# remote_light.net
KiCad netlist of a schematic drawn in EAGLE
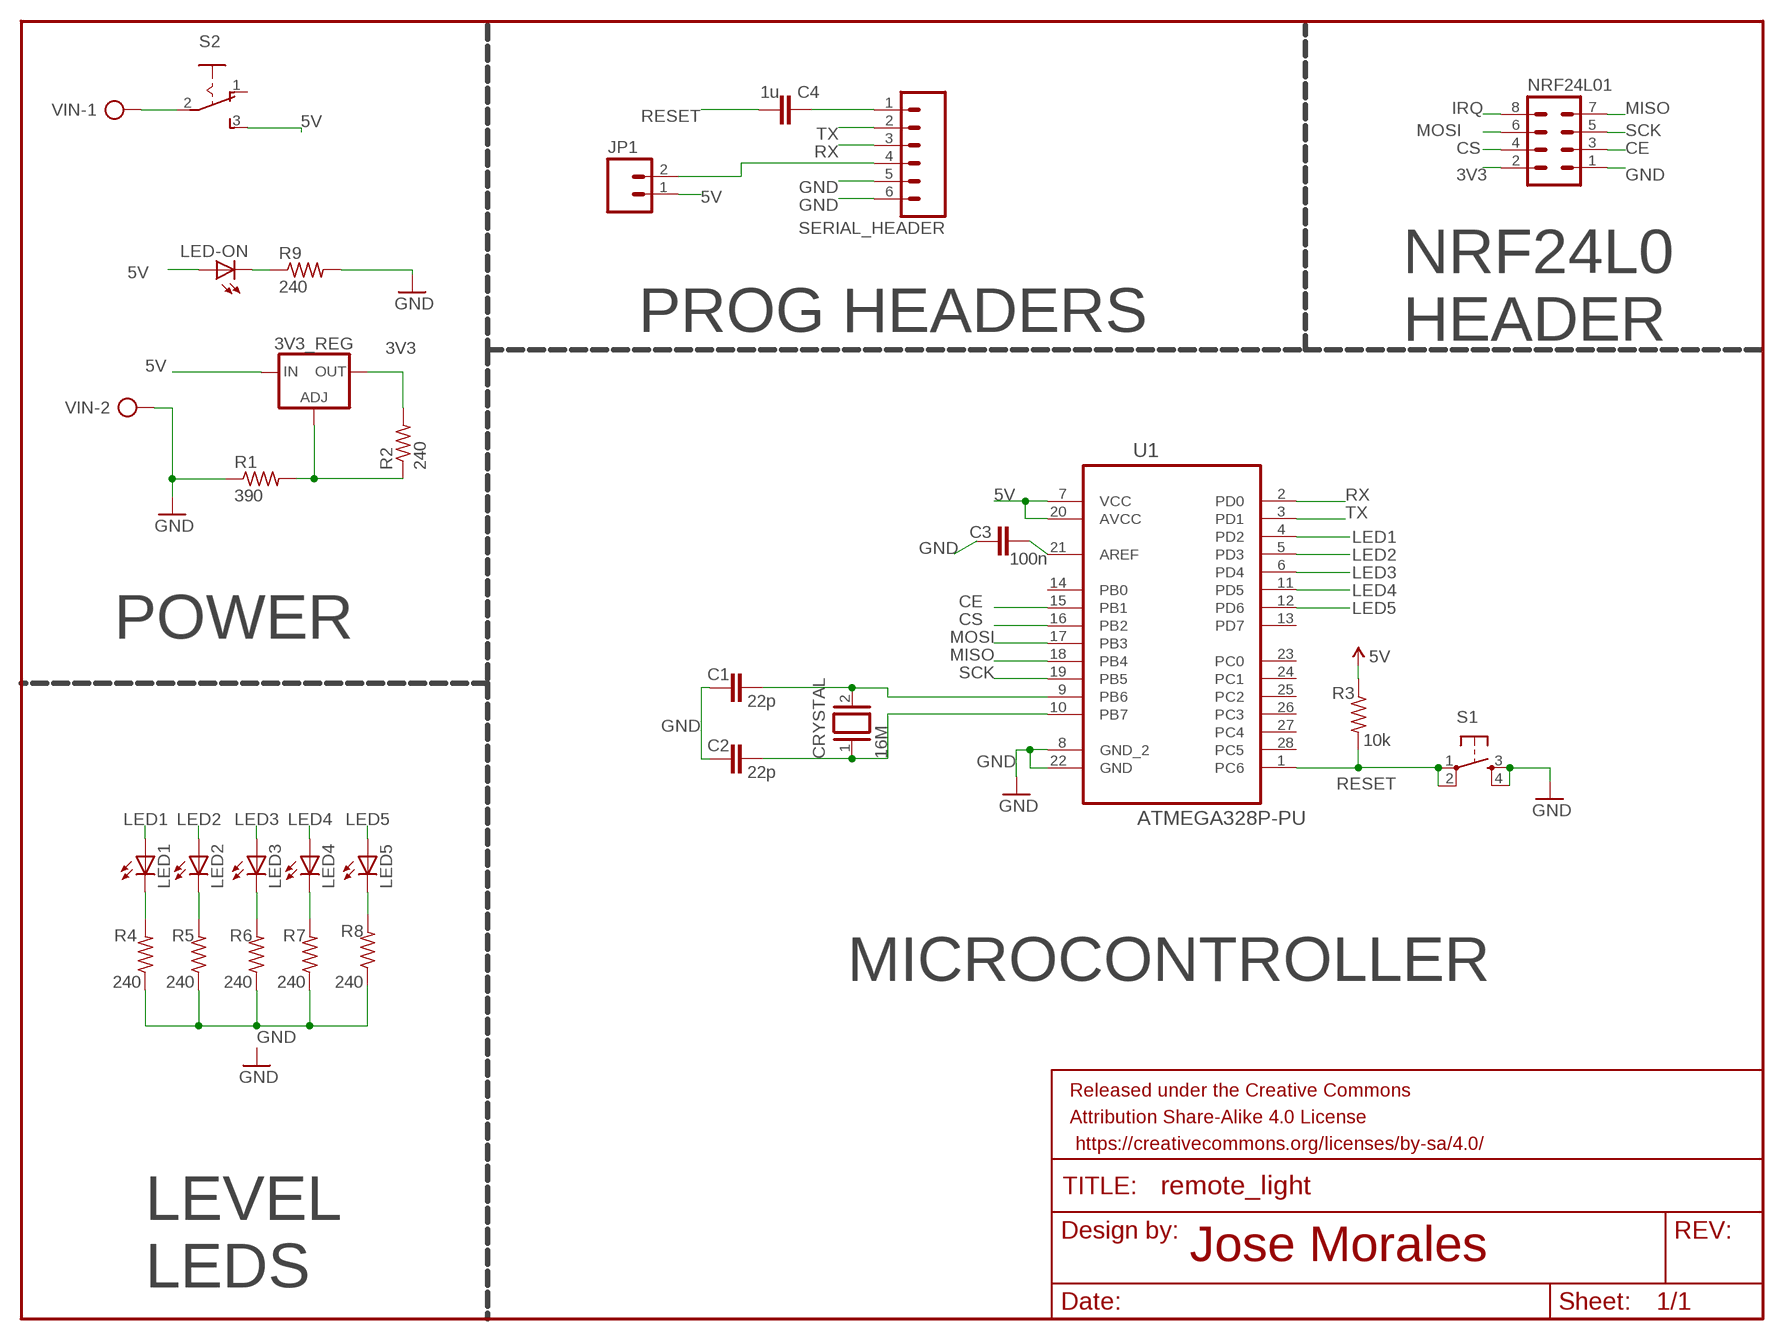
[diagram p0: schematic, sheet 1]

(export (version "E")
  (design (tool "Eeschema 10.0.6"))
  (components
    (comp (ref "C1")
      (value "22p")
      (footprint "eagle-import:C050-025X075")
      (libsource (lib "eagle-import") (part "C-EU050-025X075"))
    )
    (comp (ref "C2")
      (value "22p")
      (footprint "eagle-import:C050-025X075")
      (libsource (lib "eagle-import") (part "C-EU050-025X075"))
    )
    (comp (ref "C3")
      (value "100n")
      (footprint "eagle-import:C050-025X075")
      (libsource (lib "eagle-import") (part "C-EU050-025X075"))
    )
    (comp (ref "C4")
      (value "1u")
      (footprint "eagle-import:C050-025X075")
      (libsource (lib "eagle-import") (part "C-EU050-025X075"))
    )
    (comp (ref "CRYSTAL")
      (value "16M")
      (footprint "eagle-import:QS")
      (libsource (lib "eagle-import") (part "XTAL/S"))
    )
    (comp (ref "FRAME11")
      (value "FRAME-LETTER")
      (footprint "eagle-import:CREATIVE_COMMONS")
      (fields (field (name "DESIGNER") "NAME"))
      (libsource (lib "eagle-import") (part "FRAME-LETTER"))
    )
    (comp (ref "JP1")
      (value "M02LOCK")
      (footprint "eagle-import:1X02_LOCK")
      (libsource (lib "eagle-import") (part "M02LOCK"))
    )
    (comp (ref "LED-ON")
      (value "LED5MM")
      (footprint "eagle-import:LED5MM")
      (libsource (lib "eagle-import") (part "LED5MM"))
    )
    (comp (ref "LED1")
      (value "LED5MM")
      (footprint "eagle-import:LED5MM")
      (libsource (lib "eagle-import") (part "LED5MM"))
    )
    (comp (ref "LED2")
      (value "LED5MM")
      (footprint "eagle-import:LED5MM")
      (libsource (lib "eagle-import") (part "LED5MM"))
    )
    (comp (ref "LED3")
      (value "LED5MM")
      (footprint "eagle-import:LED5MM")
      (libsource (lib "eagle-import") (part "LED5MM"))
    )
    (comp (ref "LED4")
      (value "LED5MM")
      (footprint "eagle-import:LED5MM")
      (libsource (lib "eagle-import") (part "LED5MM"))
    )
    (comp (ref "LED5")
      (value "LED5MM")
      (footprint "eagle-import:LED5MM")
      (libsource (lib "eagle-import") (part "LED5MM"))
    )
    (comp (ref "LM317")
      (value "3V3_REG")
      (footprint "eagle-import:317TS")
      (libsource (lib "eagle-import") (part "LM317TS"))
    )
    (comp (ref "NRF24L01")
      (value "MA04-2")
      (footprint "eagle-import:MA04-2")
      (libsource (lib "eagle-import") (part "MA04-2"))
    )
    (comp (ref "R1")
      (value "390")
      (footprint "eagle-import:0207_12")
      (libsource (lib "eagle-import") (part "R-US_0207/12"))
    )
    (comp (ref "R2")
      (value "240")
      (footprint "eagle-import:0207_12")
      (libsource (lib "eagle-import") (part "R-US_0207/12"))
    )
    (comp (ref "R3")
      (value "10k")
      (footprint "eagle-import:0207_12")
      (libsource (lib "eagle-import") (part "R-US_0207/12"))
    )
    (comp (ref "R4")
      (value "240")
      (footprint "eagle-import:0207_12")
      (libsource (lib "eagle-import") (part "R-US_0207/12"))
    )
    (comp (ref "R5")
      (value "240")
      (footprint "eagle-import:0207_12")
      (libsource (lib "eagle-import") (part "R-US_0207/12"))
    )
    (comp (ref "R6")
      (value "240")
      (footprint "eagle-import:0207_12")
      (libsource (lib "eagle-import") (part "R-US_0207/12"))
    )
    (comp (ref "R7")
      (value "240")
      (footprint "eagle-import:0207_12")
      (libsource (lib "eagle-import") (part "R-US_0207/12"))
    )
    (comp (ref "R8")
      (value "240")
      (footprint "eagle-import:0207_12")
      (libsource (lib "eagle-import") (part "R-US_0207/12"))
    )
    (comp (ref "R9")
      (value "240")
      (footprint "eagle-import:0207_12")
      (libsource (lib "eagle-import") (part "R-US_0207/12"))
    )
    (comp (ref "S1")
      (value "TAC_SWITCHPTH")
      (footprint "eagle-import:TACTILE-PTH")
      (libsource (lib "eagle-import") (part "TAC_SWITCHPTH"))
    )
    (comp (ref "S2")
      (value "255SB")
      (footprint "eagle-import:255SB")
      (libsource (lib "eagle-import") (part "255SB"))
    )
    (comp (ref "SERIAL_HEADER")
      (value "M06POLAR")
      (footprint "eagle-import:MOLEX-1X6")
      (libsource (lib "eagle-import") (part "M06POLAR"))
    )
    (comp (ref "U1")
      (value "ATMEGA328P-PU")
      (footprint "eagle-import:DIP254P762X457-28")
      (libsource (lib "eagle-import") (part "ATMEGA328P-PU"))
    )
    (comp (ref "VIN")
      (value "AK300/2")
      (footprint "eagle-import:AK300_2")
      (libsource (lib "eagle-import") (part "AK300/2"))
    )
  )
  (nets
    (net (code "1") (name "/3V3") (class "Default")
      (node (ref "LM317") (pin "2") (pinfunction "OUT_2") (pintype "passive"))
      (node (ref "NRF24L01") (pin "2") (pinfunction "2_2") (pintype "passive"))
      (node (ref "R2") (pin "2") (pinfunction "2_2") (pintype "passive"))
    )
    (net (code "2") (name "/CE") (class "Default")
      (node (ref "NRF24L01") (pin "3") (pinfunction "3_3") (pintype "passive"))
      (node (ref "U1") (pin "15") (pinfunction "PB1_15") (pintype "bidirectional"))
    )
    (net (code "3") (name "/CS") (class "Default")
      (node (ref "NRF24L01") (pin "4") (pinfunction "4_4") (pintype "passive"))
      (node (ref "U1") (pin "16") (pinfunction "PB2_16") (pintype "bidirectional"))
    )
    (net (code "4") (name "/IRQ") (class "Default")
      (node (ref "NRF24L01") (pin "8") (pinfunction "8_8") (pintype "passive"))
    )
    (net (code "5") (name "/LED1") (class "Default")
      (node (ref "LED1") (pin "A") (pinfunction "A_A") (pintype "passive"))
      (node (ref "U1") (pin "4") (pinfunction "PD2_4") (pintype "bidirectional"))
    )
    (net (code "6") (name "/LED2") (class "Default")
      (node (ref "LED2") (pin "A") (pinfunction "A_A") (pintype "passive"))
      (node (ref "U1") (pin "5") (pinfunction "PD3_5") (pintype "bidirectional"))
    )
    (net (code "7") (name "/LED3") (class "Default")
      (node (ref "LED3") (pin "A") (pinfunction "A_A") (pintype "passive"))
      (node (ref "U1") (pin "6") (pinfunction "PD4_6") (pintype "bidirectional"))
    )
    (net (code "8") (name "/LED4") (class "Default")
      (node (ref "LED4") (pin "A") (pinfunction "A_A") (pintype "passive"))
      (node (ref "U1") (pin "11") (pinfunction "PD5_11") (pintype "bidirectional"))
    )
    (net (code "9") (name "/LED5") (class "Default")
      (node (ref "LED5") (pin "A") (pinfunction "A_A") (pintype "passive"))
      (node (ref "U1") (pin "12") (pinfunction "PD6_12") (pintype "bidirectional"))
    )
    (net (code "10") (name "/MISO") (class "Default")
      (node (ref "NRF24L01") (pin "7") (pinfunction "7_7") (pintype "passive"))
      (node (ref "U1") (pin "18") (pinfunction "PB4_18") (pintype "bidirectional"))
    )
    (net (code "11") (name "/MOSI") (class "Default")
      (node (ref "NRF24L01") (pin "6") (pinfunction "6_6") (pintype "passive"))
      (node (ref "U1") (pin "17") (pinfunction "PB3_17") (pintype "bidirectional"))
    )
    (net (code "12") (name "/RESET") (class "Default")
      (node (ref "C4") (pin "1") (pinfunction "1_1") (pintype "passive"))
      (node (ref "R3") (pin "2") (pinfunction "2_2") (pintype "passive"))
      (node (ref "S1") (pin "1") (pinfunction "1_1") (pintype "passive"))
      (node (ref "S1") (pin "2") (pinfunction "2_2") (pintype "passive"))
      (node (ref "U1") (pin "1") (pinfunction "PC6_1") (pintype "bidirectional"))
    )
    (net (code "13") (name "/RX") (class "Default")
      (node (ref "SERIAL_HEADER") (pin "3") (pinfunction "3_3") (pintype "passive"))
      (node (ref "U1") (pin "2") (pinfunction "PD0_2") (pintype "bidirectional"))
    )
    (net (code "14") (name "/SCK") (class "Default")
      (node (ref "NRF24L01") (pin "5") (pinfunction "5_5") (pintype "passive"))
      (node (ref "U1") (pin "19") (pinfunction "PB5_19") (pintype "bidirectional"))
    )
    (net (code "15") (name "/TX") (class "Default")
      (node (ref "SERIAL_HEADER") (pin "2") (pinfunction "2_2") (pintype "passive"))
      (node (ref "U1") (pin "3") (pinfunction "PD1_3") (pintype "bidirectional"))
    )
    (net (code "16") (name "5V") (class "Default")
      (node (ref "JP1") (pin "1") (pinfunction "1_1") (pintype "passive"))
      (node (ref "LED-ON") (pin "A") (pinfunction "A_A") (pintype "passive"))
      (node (ref "LM317") (pin "3") (pinfunction "IN_3") (pintype "input"))
      (node (ref "R3") (pin "1") (pinfunction "1_1") (pintype "passive"))
      (node (ref "S2") (pin "3") (pinfunction "S_3") (pintype "passive"))
      (node (ref "U1") (pin "20") (pinfunction "AVCC_20") (pintype "power_in"))
      (node (ref "U1") (pin "7") (pinfunction "VCC_7") (pintype "power_in"))
    )
    (net (code "17") (name "GND") (class "Default")
      (node (ref "C1") (pin "2") (pinfunction "2_2") (pintype "passive"))
      (node (ref "C2") (pin "2") (pinfunction "2_2") (pintype "passive"))
      (node (ref "C3") (pin "2") (pinfunction "2_2") (pintype "passive"))
      (node (ref "NRF24L01") (pin "1") (pinfunction "1_1") (pintype "passive"))
      (node (ref "R1") (pin "1") (pinfunction "1_1") (pintype "passive"))
      (node (ref "R4") (pin "1") (pinfunction "1_1") (pintype "passive"))
      (node (ref "R5") (pin "1") (pinfunction "1_1") (pintype "passive"))
      (node (ref "R6") (pin "1") (pinfunction "1_1") (pintype "passive"))
      (node (ref "R7") (pin "1") (pinfunction "1_1") (pintype "passive"))
      (node (ref "R8") (pin "1") (pinfunction "1_1") (pintype "passive"))
      (node (ref "R9") (pin "2") (pinfunction "2_2") (pintype "passive"))
      (node (ref "S1") (pin "3") (pinfunction "3_3") (pintype "passive"))
      (node (ref "S1") (pin "4") (pinfunction "4_4") (pintype "passive"))
      (node (ref "SERIAL_HEADER") (pin "5") (pinfunction "5_5") (pintype "passive"))
      (node (ref "SERIAL_HEADER") (pin "6") (pinfunction "6_6") (pintype "passive"))
      (node (ref "U1") (pin "22") (pinfunction "GND_22") (pintype "passive"))
      (node (ref "U1") (pin "8") (pinfunction "GND_2_8") (pintype "passive"))
      (node (ref "VIN") (pin "2") (pinfunction "KL_2") (pintype "passive"))
    )
    (net (code "18") (name "Net-(C4-Pad2)") (class "Default")
      (node (ref "C4") (pin "2") (pinfunction "2_2") (pintype "passive"))
      (node (ref "SERIAL_HEADER") (pin "1") (pinfunction "1_1") (pintype "passive"))
    )
    (net (code "19") (name "Net-(JP1-Pad2)") (class "Default")
      (node (ref "JP1") (pin "2") (pinfunction "2_2") (pintype "passive"))
      (node (ref "SERIAL_HEADER") (pin "4") (pinfunction "4_4") (pintype "passive"))
    )
    (net (code "20") (name "Net-(LED-ON-C)") (class "Default")
      (node (ref "LED-ON") (pin "K") (pinfunction "C_K") (pintype "passive"))
      (node (ref "R9") (pin "1") (pinfunction "1_1") (pintype "passive"))
    )
    (net (code "21") (name "Net-(LED1-C)") (class "Default")
      (node (ref "LED1") (pin "K") (pinfunction "C_K") (pintype "passive"))
      (node (ref "R4") (pin "2") (pinfunction "2_2") (pintype "passive"))
    )
    (net (code "22") (name "Net-(LED2-C)") (class "Default")
      (node (ref "LED2") (pin "K") (pinfunction "C_K") (pintype "passive"))
      (node (ref "R5") (pin "2") (pinfunction "2_2") (pintype "passive"))
    )
    (net (code "23") (name "Net-(LED3-C)") (class "Default")
      (node (ref "LED3") (pin "K") (pinfunction "C_K") (pintype "passive"))
      (node (ref "R6") (pin "2") (pinfunction "2_2") (pintype "passive"))
    )
    (net (code "24") (name "Net-(LED4-C)") (class "Default")
      (node (ref "LED4") (pin "K") (pinfunction "C_K") (pintype "passive"))
      (node (ref "R7") (pin "2") (pinfunction "2_2") (pintype "passive"))
    )
    (net (code "25") (name "Net-(LED5-C)") (class "Default")
      (node (ref "LED5") (pin "K") (pinfunction "C_K") (pintype "passive"))
      (node (ref "R8") (pin "2") (pinfunction "2_2") (pintype "passive"))
    )
    (net (code "26") (name "Net-(LM317-ADJ)") (class "Default")
      (node (ref "LM317") (pin "1") (pinfunction "ADJ_1") (pintype "input"))
      (node (ref "R1") (pin "2") (pinfunction "2_2") (pintype "passive"))
      (node (ref "R2") (pin "1") (pinfunction "1_1") (pintype "passive"))
    )
    (net (code "27") (name "Net-(S2-P)") (class "Default")
      (node (ref "S2") (pin "2") (pinfunction "P_2") (pintype "passive"))
      (node (ref "VIN") (pin "1") (pinfunction "KL_1") (pintype "passive"))
    )
    (net (code "28") (name "Net-(U1-AREF)") (class "Default")
      (node (ref "C3") (pin "1") (pinfunction "1_1") (pintype "passive"))
      (node (ref "U1") (pin "21") (pinfunction "AREF_21") (pintype "input"))
    )
    (net (code "29") (name "Net-(U1-PB6)") (class "Default")
      (node (ref "C1") (pin "1") (pinfunction "1_1") (pintype "passive"))
      (node (ref "CRYSTAL") (pin "2") (pinfunction "2_2") (pintype "passive"))
      (node (ref "U1") (pin "9") (pinfunction "PB6_9") (pintype "bidirectional"))
    )
    (net (code "30") (name "Net-(U1-PB7)") (class "Default")
      (node (ref "C2") (pin "1") (pinfunction "1_1") (pintype "passive"))
      (node (ref "CRYSTAL") (pin "1") (pinfunction "1_1") (pintype "passive"))
      (node (ref "U1") (pin "10") (pinfunction "PB7_10") (pintype "bidirectional"))
    )
    (net (code "31") (name "unconnected-(S2-O-Pad1)") (class "Default")
      (node (ref "S2") (pin "1") (pinfunction "O_1") (pintype "passive"))
    )
    (net (code "32") (name "unconnected-(U1-PB0-Pad14)") (class "Default")
      (node (ref "U1") (pin "14") (pinfunction "PB0_14") (pintype "bidirectional"))
    )
    (net (code "33") (name "unconnected-(U1-PC0-Pad23)") (class "Default")
      (node (ref "U1") (pin "23") (pinfunction "PC0_23") (pintype "bidirectional"))
    )
    (net (code "34") (name "unconnected-(U1-PC1-Pad24)") (class "Default")
      (node (ref "U1") (pin "24") (pinfunction "PC1_24") (pintype "bidirectional"))
    )
    (net (code "35") (name "unconnected-(U1-PC2-Pad25)") (class "Default")
      (node (ref "U1") (pin "25") (pinfunction "PC2_25") (pintype "bidirectional"))
    )
    (net (code "36") (name "unconnected-(U1-PC3-Pad26)") (class "Default")
      (node (ref "U1") (pin "26") (pinfunction "PC3_26") (pintype "bidirectional"))
    )
    (net (code "37") (name "unconnected-(U1-PC4-Pad27)") (class "Default")
      (node (ref "U1") (pin "27") (pinfunction "PC4_27") (pintype "bidirectional"))
    )
    (net (code "38") (name "unconnected-(U1-PC5-Pad28)") (class "Default")
      (node (ref "U1") (pin "28") (pinfunction "PC5_28") (pintype "bidirectional"))
    )
    (net (code "39") (name "unconnected-(U1-PD7-Pad13)") (class "Default")
      (node (ref "U1") (pin "13") (pinfunction "PD7_13") (pintype "bidirectional"))
    )
  )
)
